# New_SERV_OPEN8_SOTB.net
KiCad netlist of a schematic drawn in EAGLE
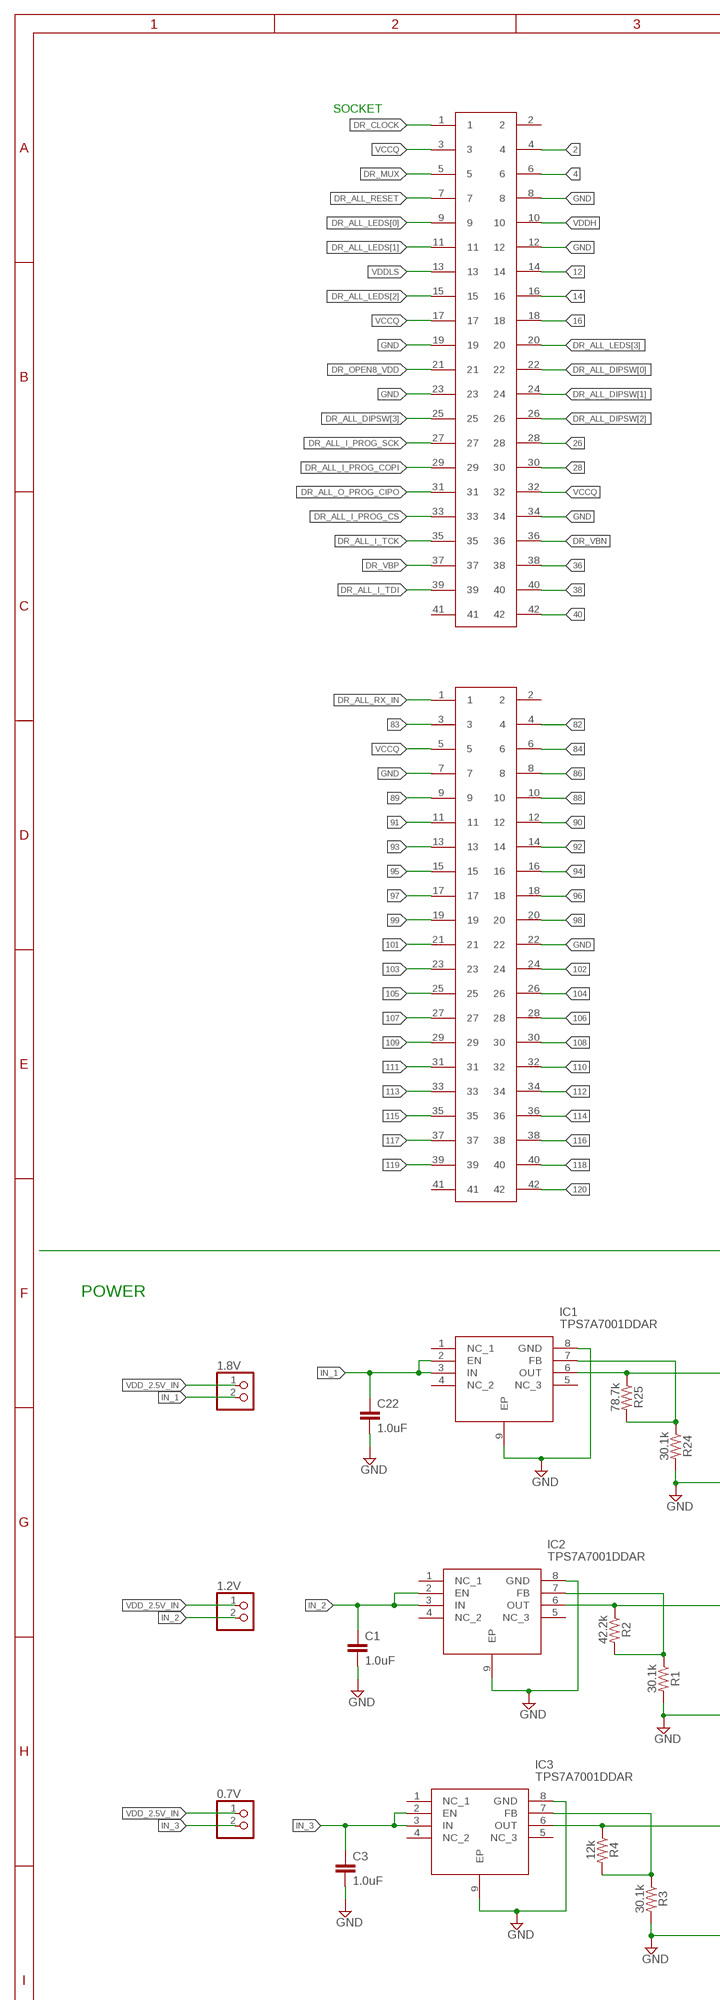
[diagram p0: schematic, sheet 1, part 1 of 2]
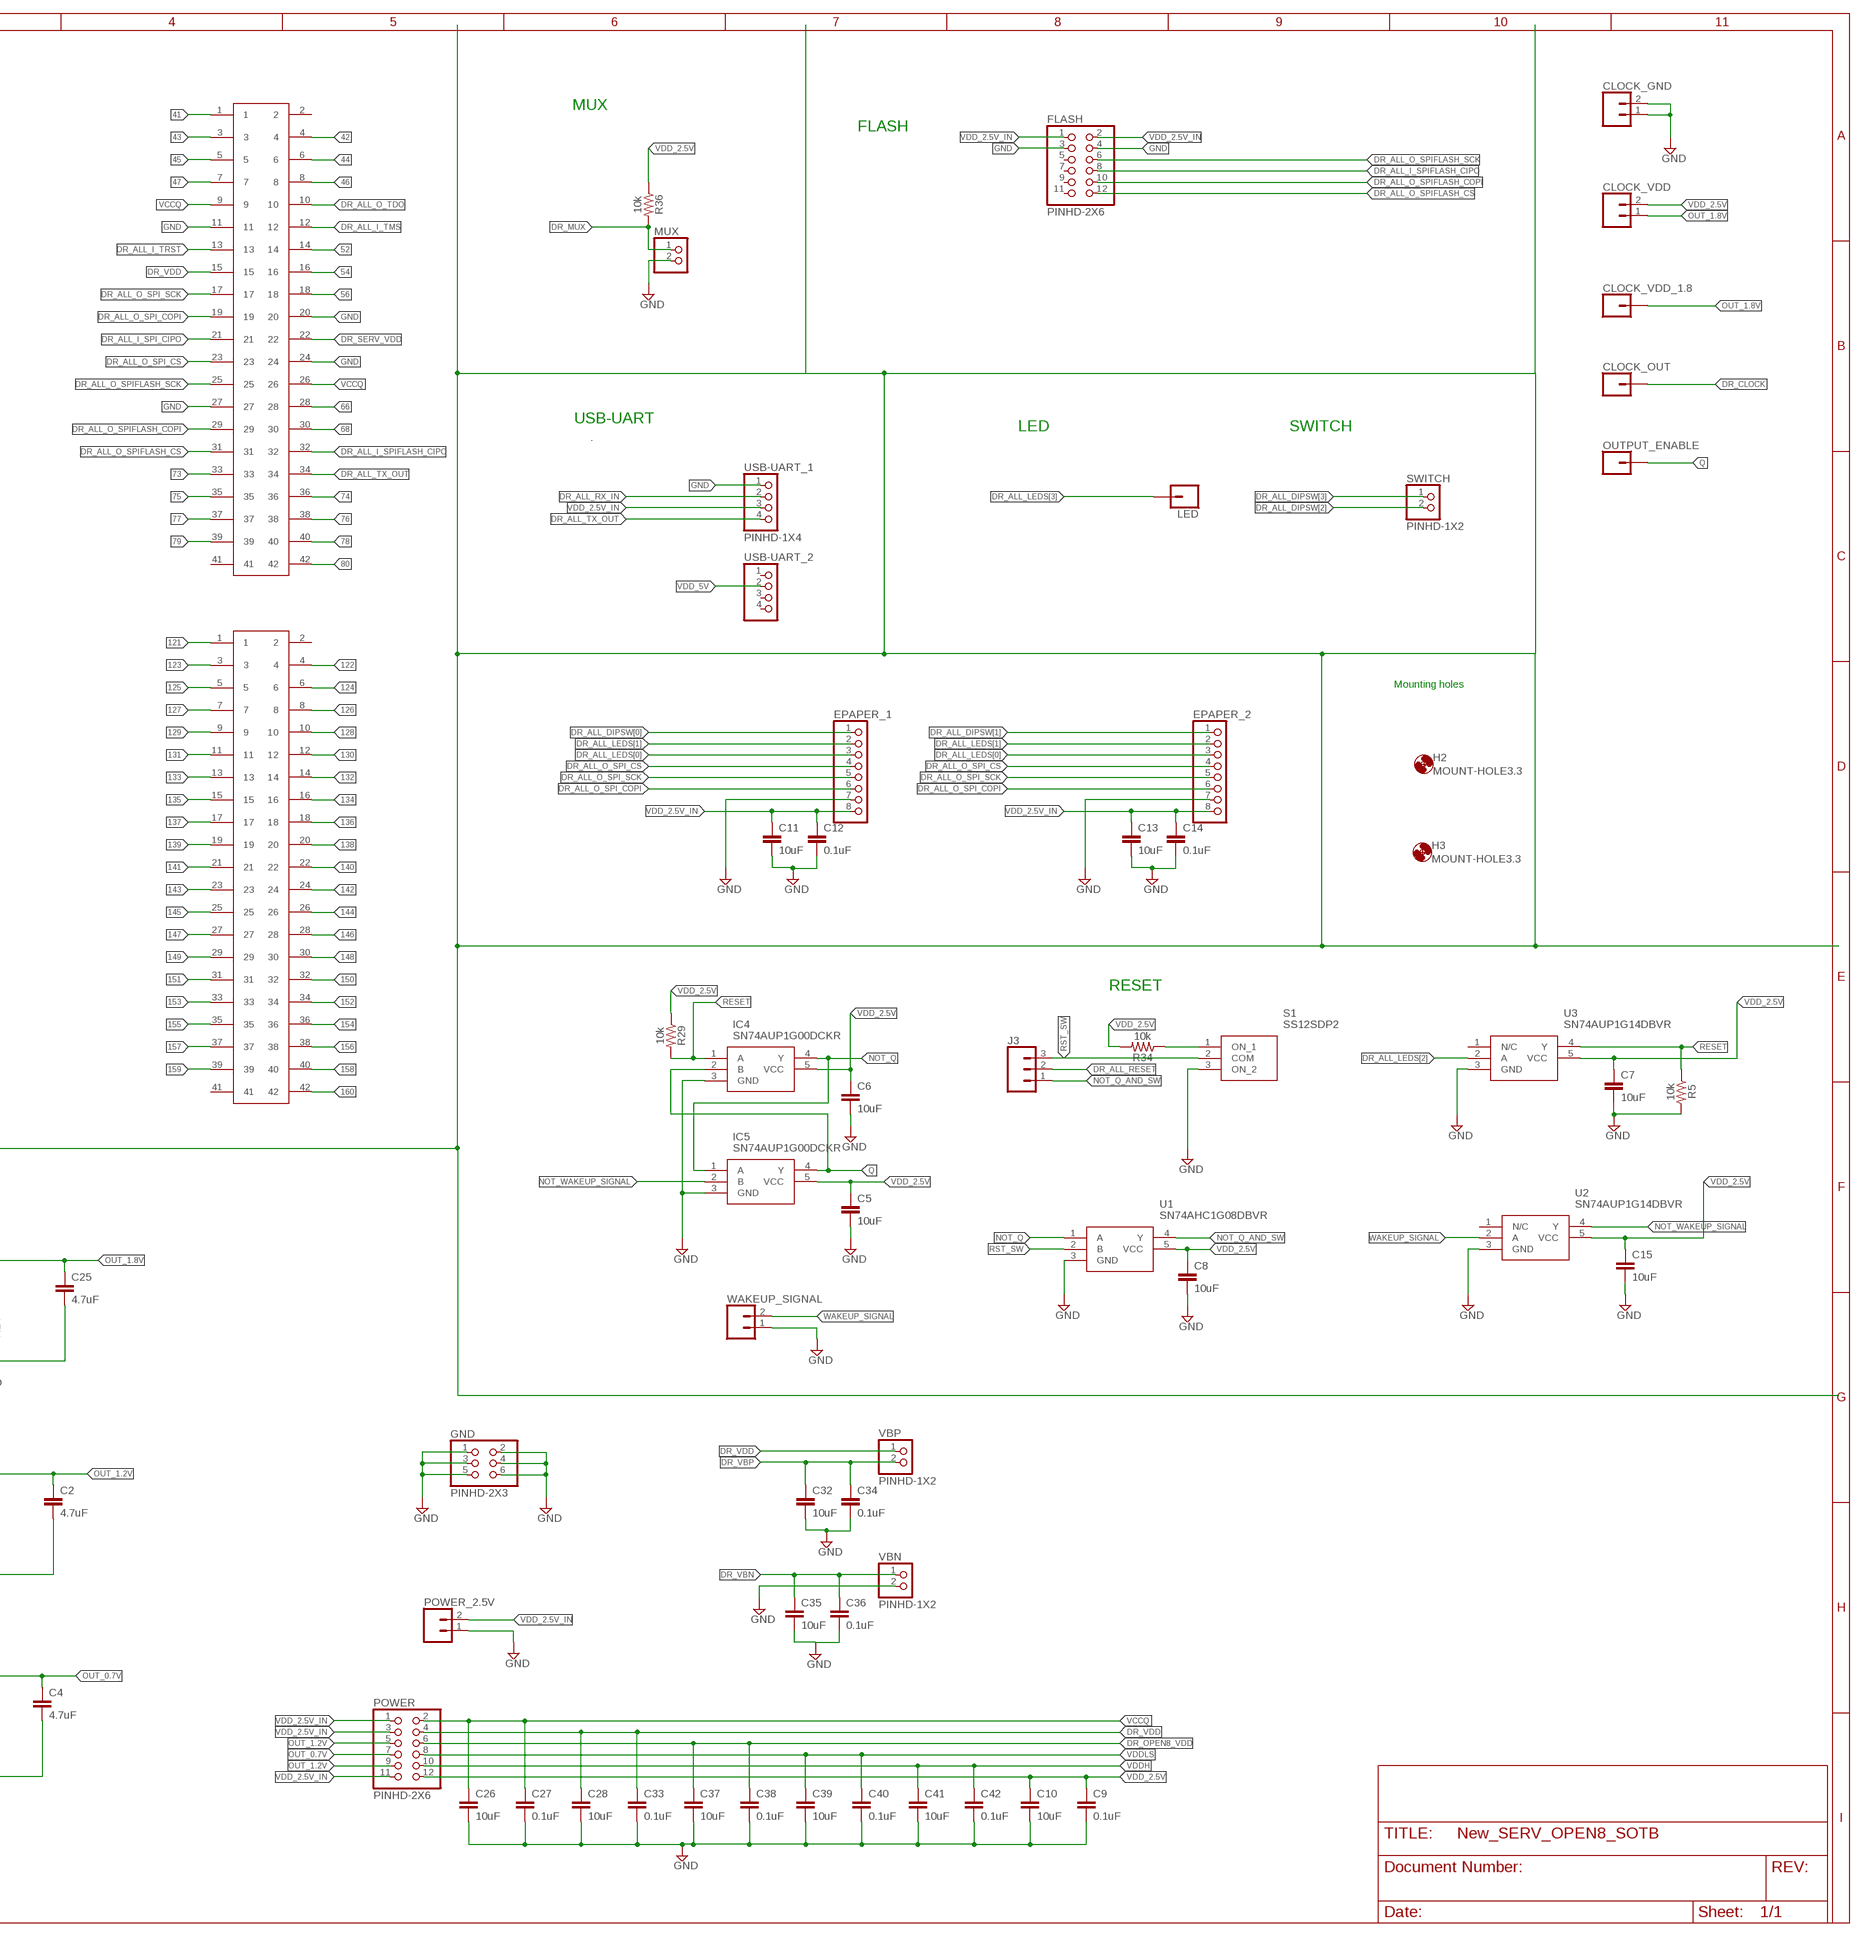
[diagram p1: schematic, sheet 1, part 2 of 2]

(export (version "E")
  (design (tool "Eeschema 10.0.6"))
  (components
    (comp (ref "0.7V")
      (value "PINHD-1X2")
      (footprint "eagle-import:1X02")
      (libsource (lib "eagle-import") (part "pinhead_325_PINHD-1X2"))
    )
    (comp (ref "1.2V")
      (value "PINHD-1X2")
      (footprint "eagle-import:1X02")
      (libsource (lib "eagle-import") (part "pinhead_325_PINHD-1X2"))
    )
    (comp (ref "1.8V")
      (value "PINHD-1X2")
      (footprint "eagle-import:1X02")
      (libsource (lib "eagle-import") (part "pinhead_325_PINHD-1X2"))
    )
    (comp (ref "C1")
      (value "1.0uF")
      (footprint "eagle-import:0805")
      (libsource (lib "eagle-import") (part "1.0UF-0805-25V-(+80/-20%)"))
    )
    (comp (ref "C2")
      (value "4.7uF")
      (footprint "eagle-import:0805")
      (libsource (lib "eagle-import") (part "1.0UF-0805-25V-(+80/-20%)"))
    )
    (comp (ref "C3")
      (value "1.0uF")
      (footprint "eagle-import:0805")
      (libsource (lib "eagle-import") (part "1.0UF-0805-25V-(+80/-20%)"))
    )
    (comp (ref "C4")
      (value "4.7uF")
      (footprint "eagle-import:0805")
      (libsource (lib "eagle-import") (part "1.0UF-0805-25V-(+80/-20%)"))
    )
    (comp (ref "C5")
      (value "10uF")
      (footprint "eagle-import:0805")
      (libsource (lib "eagle-import") (part "1.0UF-0805-25V-(+80/-20%)"))
    )
    (comp (ref "C6")
      (value "10uF")
      (footprint "eagle-import:0805")
      (libsource (lib "eagle-import") (part "1.0UF-0805-25V-(+80/-20%)"))
    )
    (comp (ref "C7")
      (value "10uF")
      (footprint "eagle-import:0805")
      (libsource (lib "eagle-import") (part "1.0UF-0805-25V-(+80/-20%)"))
    )
    (comp (ref "C8")
      (value "10uF")
      (footprint "eagle-import:0805")
      (libsource (lib "eagle-import") (part "1.0UF-0805-25V-(+80/-20%)"))
    )
    (comp (ref "C9")
      (value "0.1uF")
      (footprint "eagle-import:0805")
      (libsource (lib "eagle-import") (part "1.0UF-0805-25V-(+80/-20%)"))
    )
    (comp (ref "C10")
      (value "10uF")
      (footprint "eagle-import:0805")
      (libsource (lib "eagle-import") (part "1.0UF-0805-25V-(+80/-20%)"))
    )
    (comp (ref "C11")
      (value "10uF")
      (footprint "eagle-import:0805")
      (libsource (lib "eagle-import") (part "1.0UF-0805-25V-(+80/-20%)"))
    )
    (comp (ref "C12")
      (value "0.1uF")
      (footprint "eagle-import:0805")
      (libsource (lib "eagle-import") (part "1.0UF-0805-25V-(+80/-20%)"))
    )
    (comp (ref "C13")
      (value "10uF")
      (footprint "eagle-import:0805")
      (libsource (lib "eagle-import") (part "1.0UF-0805-25V-(+80/-20%)"))
    )
    (comp (ref "C14")
      (value "0.1uF")
      (footprint "eagle-import:0805")
      (libsource (lib "eagle-import") (part "1.0UF-0805-25V-(+80/-20%)"))
    )
    (comp (ref "C15")
      (value "10uF")
      (footprint "eagle-import:0805")
      (libsource (lib "eagle-import") (part "1.0UF-0805-25V-(+80/-20%)"))
    )
    (comp (ref "C22")
      (value "1.0uF")
      (footprint "eagle-import:0805")
      (libsource (lib "eagle-import") (part "1.0UF-0805-25V-(+80/-20%)"))
    )
    (comp (ref "C25")
      (value "4.7uF")
      (footprint "eagle-import:0805")
      (libsource (lib "eagle-import") (part "1.0UF-0805-25V-(+80/-20%)"))
    )
    (comp (ref "C26")
      (value "10uF")
      (footprint "eagle-import:0805")
      (libsource (lib "eagle-import") (part "1.0UF-0805-25V-(+80/-20%)"))
    )
    (comp (ref "C27")
      (value "0.1uF")
      (footprint "eagle-import:0805")
      (libsource (lib "eagle-import") (part "1.0UF-0805-25V-(+80/-20%)"))
    )
    (comp (ref "C28")
      (value "10uF")
      (footprint "eagle-import:0805")
      (libsource (lib "eagle-import") (part "1.0UF-0805-25V-(+80/-20%)"))
    )
    (comp (ref "C32")
      (value "10uF")
      (footprint "eagle-import:0805")
      (libsource (lib "eagle-import") (part "1.0UF-0805-25V-(+80/-20%)"))
    )
    (comp (ref "C33")
      (value "0.1uF")
      (footprint "eagle-import:0805")
      (libsource (lib "eagle-import") (part "1.0UF-0805-25V-(+80/-20%)"))
    )
    (comp (ref "C34")
      (value "0.1uF")
      (footprint "eagle-import:0805")
      (libsource (lib "eagle-import") (part "1.0UF-0805-25V-(+80/-20%)"))
    )
    (comp (ref "C35")
      (value "10uF")
      (footprint "eagle-import:0805")
      (libsource (lib "eagle-import") (part "1.0UF-0805-25V-(+80/-20%)"))
    )
    (comp (ref "C36")
      (value "0.1uF")
      (footprint "eagle-import:0805")
      (libsource (lib "eagle-import") (part "1.0UF-0805-25V-(+80/-20%)"))
    )
    (comp (ref "C37")
      (value "10uF")
      (footprint "eagle-import:0805")
      (libsource (lib "eagle-import") (part "1.0UF-0805-25V-(+80/-20%)"))
    )
    (comp (ref "C38")
      (value "0.1uF")
      (footprint "eagle-import:0805")
      (libsource (lib "eagle-import") (part "1.0UF-0805-25V-(+80/-20%)"))
    )
    (comp (ref "C39")
      (value "10uF")
      (footprint "eagle-import:0805")
      (libsource (lib "eagle-import") (part "1.0UF-0805-25V-(+80/-20%)"))
    )
    (comp (ref "C40")
      (value "0.1uF")
      (footprint "eagle-import:0805")
      (libsource (lib "eagle-import") (part "1.0UF-0805-25V-(+80/-20%)"))
    )
    (comp (ref "C41")
      (value "10uF")
      (footprint "eagle-import:0805")
      (libsource (lib "eagle-import") (part "1.0UF-0805-25V-(+80/-20%)"))
    )
    (comp (ref "C42")
      (value "0.1uF")
      (footprint "eagle-import:0805")
      (libsource (lib "eagle-import") (part "1.0UF-0805-25V-(+80/-20%)"))
    )
    (comp (ref "CLOCK_GND")
      (value "CONN_02")
      (footprint "eagle-import:1X02")
      (libsource (lib "eagle-import") (part "CONN_02"))
    )
    (comp (ref "CLOCK_OUT")
      (value "CONN_01")
      (footprint "eagle-import:1X01")
      (libsource (lib "eagle-import") (part "CONN_01"))
    )
    (comp (ref "CLOCK_VDD")
      (value "CONN_02")
      (footprint "eagle-import:1X02")
      (libsource (lib "eagle-import") (part "CONN_02"))
    )
    (comp (ref "CLOCK_VDD_1.8")
      (value "CONN_01")
      (footprint "eagle-import:1X01")
      (libsource (lib "eagle-import") (part "CONN_01"))
    )
    (comp (ref "EPAPER_1")
      (value "PINHD-1X8")
      (footprint "eagle-import:1X08")
      (libsource (lib "eagle-import") (part "PINHD-1X8"))
    )
    (comp (ref "EPAPER_2")
      (value "PINHD-1X8")
      (footprint "eagle-import:1X08")
      (libsource (lib "eagle-import") (part "PINHD-1X8"))
    )
    (comp (ref "FLASH")
      (value "PINHD-2X6")
      (footprint "eagle-import:2X06")
      (libsource (lib "eagle-import") (part "PINHD-2X6"))
    )
    (comp (ref "GND")
      (value "PINHD-2X3")
      (footprint "eagle-import:2X03")
      (libsource (lib "eagle-import") (part "PINHD-2X3"))
    )
    (comp (ref "H2")
      (value "MOUNT-HOLE3.3")
      (footprint "eagle-import:3,3")
      (libsource (lib "eagle-import") (part "MOUNT-HOLE3.3"))
    )
    (comp (ref "H3")
      (value "MOUNT-HOLE3.3")
      (footprint "eagle-import:3,3")
      (libsource (lib "eagle-import") (part "MOUNT-HOLE3.3"))
    )
    (comp (ref "IC1")
      (value "TPS7A7001DDAR")
      (footprint "eagle-import:SOIC127P600X170-9N")
      (fields (field (name "MOUSER_PART_NUMBER") "595-TPS7A7001DDAR"))
      (libsource (lib "eagle-import") (part "TPS7A7001DDAR"))
    )
    (comp (ref "IC2")
      (value "TPS7A7001DDAR")
      (footprint "eagle-import:SOIC127P600X170-9N")
      (fields (field (name "MOUSER_PART_NUMBER") "595-TPS7A7001DDAR"))
      (libsource (lib "eagle-import") (part "TPS7A7001DDAR"))
    )
    (comp (ref "IC3")
      (value "TPS7A7001DDAR")
      (footprint "eagle-import:SOIC127P600X170-9N")
      (fields (field (name "MOUSER_PART_NUMBER") "595-TPS7A7001DDAR"))
      (libsource (lib "eagle-import") (part "TPS7A7001DDAR"))
    )
    (comp (ref "IC4")
      (value "SN74AUP1G00DCKR")
      (footprint "eagle-import:SOT65P210X110-5N")
      (fields (field (name "MOUSER_PART_NUMBER") "595-SN74AUP1G00DCKR"))
      (libsource (lib "eagle-import") (part "SN74AUP1G00DCKR"))
    )
    (comp (ref "IC5")
      (value "SN74AUP1G00DCKR")
      (footprint "eagle-import:SOT65P210X110-5N")
      (fields (field (name "MOUSER_PART_NUMBER") "595-SN74AUP1G00DCKR"))
      (libsource (lib "eagle-import") (part "SN74AUP1G00DCKR"))
    )
    (comp (ref "J3")
      (value "CONN_03")
      (footprint "eagle-import:1X03")
      (libsource (lib "eagle-import") (part "CONN_03"))
    )
    (comp (ref "LED")
      (value "CONN_01")
      (footprint "eagle-import:1X01")
      (libsource (lib "eagle-import") (part "CONN_01"))
    )
    (comp (ref "MUX")
      (value "PINHD-1X2")
      (footprint "eagle-import:1X02")
      (libsource (lib "eagle-import") (part "pinhead_325_PINHD-1X2"))
    )
    (comp (ref "OUTPUT_ENABLE")
      (value "CONN_01")
      (footprint "eagle-import:1X01")
      (libsource (lib "eagle-import") (part "CONN_01"))
    )
    (comp (ref "POWER")
      (value "PINHD-2X6")
      (footprint "eagle-import:2X06")
      (libsource (lib "eagle-import") (part "PINHD-2X6"))
    )
    (comp (ref "POWER_2.5V")
      (value "CONN_02")
      (footprint "eagle-import:1X02")
      (libsource (lib "eagle-import") (part "CONN_02"))
    )
    (comp (ref "R1")
      (value "30.1k")
      (footprint "eagle-import:0805")
      (libsource (lib "eagle-import") (part "0.3OHM-0805-1/8W-1%"))
    )
    (comp (ref "R2")
      (value "42.2k")
      (footprint "eagle-import:0805")
      (libsource (lib "eagle-import") (part "0.3OHM-0805-1/8W-1%"))
    )
    (comp (ref "R3")
      (value "30.1k")
      (footprint "eagle-import:0805")
      (libsource (lib "eagle-import") (part "0.3OHM-0805-1/8W-1%"))
    )
    (comp (ref "R4")
      (value "12k")
      (footprint "eagle-import:0805")
      (libsource (lib "eagle-import") (part "0.3OHM-0805-1/8W-1%"))
    )
    (comp (ref "R5")
      (value "10k")
      (footprint "eagle-import:0805")
      (libsource (lib "eagle-import") (part "0.3OHM-0805-1/8W-1%"))
    )
    (comp (ref "R24")
      (value "30.1k")
      (footprint "eagle-import:0805")
      (libsource (lib "eagle-import") (part "0.3OHM-0805-1/8W-1%"))
    )
    (comp (ref "R25")
      (value "78.7k")
      (footprint "eagle-import:0805")
      (libsource (lib "eagle-import") (part "0.3OHM-0805-1/8W-1%"))
    )
    (comp (ref "R29")
      (value "10k")
      (footprint "eagle-import:0805")
      (libsource (lib "eagle-import") (part "0.3OHM-0805-1/8W-1%"))
    )
    (comp (ref "R34")
      (value "10k")
      (footprint "eagle-import:0805")
      (libsource (lib "eagle-import") (part "0.3OHM-0805-1/8W-1%"))
    )
    (comp (ref "R36")
      (value "10k")
      (footprint "eagle-import:0805")
      (libsource (lib "eagle-import") (part "0.3OHM-0805-1/8W-1%"))
    )
    (comp (ref "S1")
      (value "SS12SDP2")
      (footprint "eagle-import:SS12SDP2")
      (fields (field (name "MOUSER_PART_NUMBER") "633-SS12SDP2"))
      (libsource (lib "eagle-import") (part "SS12SDP2"))
    )
    (comp (ref "SWITCH")
      (value "PINHD-1X2")
      (footprint "eagle-import:1X02")
      (libsource (lib "eagle-import") (part "PINHD-1X2"))
    )
    (comp (ref "U$1")
      (value "2X41_HEADER")
      (footprint "eagle-import:2X41_HEADER")
      (libsource (lib "eagle-import") (part "2X41_HEADER"))
    )
    (comp (ref "U$2")
      (value "2X41_HEADER")
      (footprint "eagle-import:2X41_HEADER")
      (libsource (lib "eagle-import") (part "2X41_HEADER"))
    )
    (comp (ref "U$3")
      (value "2X41_HEADER")
      (footprint "eagle-import:2X41_HEADER")
      (libsource (lib "eagle-import") (part "2X41_HEADER"))
    )
    (comp (ref "U$4")
      (value "2X41_HEADER")
      (footprint "eagle-import:2X41_HEADER")
      (libsource (lib "eagle-import") (part "2X41_HEADER"))
    )
    (comp (ref "U1")
      (value "SN74AHC1G08DBVR")
      (footprint "eagle-import:SOT95P280X145-5N")
      (fields (field (name "MOUSER_PART_NUMBER") "595-SN74AHC1G08DBVR"))
      (libsource (lib "eagle-import") (part "SN74AHC1G08DBVR"))
    )
    (comp (ref "U2")
      (value "SN74AUP1G14DBVR")
      (footprint "eagle-import:SOT65P210X110-5N")
      (fields (field (name "MOUSER_PART_NUMBER") "595-SN74AUP1G14DBVR"))
      (libsource (lib "eagle-import") (part "SN74AUP1G14DBVR"))
    )
    (comp (ref "U3")
      (value "SN74AUP1G14DBVR")
      (footprint "eagle-import:SOT65P210X110-5N")
      (fields (field (name "MOUSER_PART_NUMBER") "595-SN74AUP1G14DBVR"))
      (libsource (lib "eagle-import") (part "SN74AUP1G14DBVR"))
    )
    (comp (ref "USB-UART_1")
      (value "PINHD-1X4")
      (footprint "eagle-import:1X04")
      (libsource (lib "eagle-import") (part "PINHD-1X4"))
    )
    (comp (ref "USB-UART_2")
      (value "PINHD-1X4")
      (footprint "eagle-import:1X04")
      (libsource (lib "eagle-import") (part "PINHD-1X4"))
    )
    (comp (ref "VBN")
      (value "PINHD-1X2")
      (footprint "eagle-import:1X02")
      (libsource (lib "eagle-import") (part "PINHD-1X2"))
    )
    (comp (ref "VBP")
      (value "PINHD-1X2")
      (footprint "eagle-import:1X02")
      (libsource (lib "eagle-import") (part "PINHD-1X2"))
    )
    (comp (ref "WAKEUP_SIGNAL")
      (value "CONN_02")
      (footprint "eagle-import:1X02")
      (libsource (lib "eagle-import") (part "CONN_02"))
    )
  )
  (nets
    (net (code "1") (name "2") (class "Default")
      (node (ref "U$1") (pin "4") (pinfunction "4_4") (pintype "bidirectional"))
    )
    (net (code "2") (name "4") (class "Default")
      (node (ref "U$1") (pin "6") (pinfunction "6_6") (pintype "bidirectional"))
    )
    (net (code "3") (name "12") (class "Default")
      (node (ref "U$1") (pin "14") (pinfunction "14_14") (pintype "bidirectional"))
    )
    (net (code "4") (name "14") (class "Default")
      (node (ref "U$1") (pin "16") (pinfunction "16_16") (pintype "bidirectional"))
    )
    (net (code "5") (name "16") (class "Default")
      (node (ref "U$1") (pin "18") (pinfunction "18_18") (pintype "bidirectional"))
    )
    (net (code "6") (name "26") (class "Default")
      (node (ref "U$1") (pin "28") (pinfunction "28_28") (pintype "bidirectional"))
    )
    (net (code "7") (name "28") (class "Default")
      (node (ref "U$1") (pin "30") (pinfunction "30_30") (pintype "bidirectional"))
    )
    (net (code "8") (name "36") (class "Default")
      (node (ref "U$1") (pin "38") (pinfunction "38_38") (pintype "bidirectional"))
    )
    (net (code "9") (name "38") (class "Default")
      (node (ref "U$1") (pin "40") (pinfunction "40_40") (pintype "bidirectional"))
    )
    (net (code "10") (name "40") (class "Default")
      (node (ref "U$1") (pin "42") (pinfunction "42_42") (pintype "bidirectional"))
    )
    (net (code "11") (name "41") (class "Default")
      (node (ref "U$2") (pin "1") (pinfunction "1_1") (pintype "bidirectional"))
    )
    (net (code "12") (name "42") (class "Default")
      (node (ref "U$2") (pin "4") (pinfunction "4_4") (pintype "bidirectional"))
    )
    (net (code "13") (name "43") (class "Default")
      (node (ref "U$2") (pin "3") (pinfunction "3_3") (pintype "bidirectional"))
    )
    (net (code "14") (name "44") (class "Default")
      (node (ref "U$2") (pin "6") (pinfunction "6_6") (pintype "bidirectional"))
    )
    (net (code "15") (name "45") (class "Default")
      (node (ref "U$2") (pin "5") (pinfunction "5_5") (pintype "bidirectional"))
    )
    (net (code "16") (name "46") (class "Default")
      (node (ref "U$2") (pin "8") (pinfunction "8_8") (pintype "bidirectional"))
    )
    (net (code "17") (name "47") (class "Default")
      (node (ref "U$2") (pin "7") (pinfunction "7_7") (pintype "bidirectional"))
    )
    (net (code "18") (name "52") (class "Default")
      (node (ref "U$2") (pin "14") (pinfunction "14_14") (pintype "bidirectional"))
    )
    (net (code "19") (name "54") (class "Default")
      (node (ref "U$2") (pin "16") (pinfunction "16_16") (pintype "bidirectional"))
    )
    (net (code "20") (name "56") (class "Default")
      (node (ref "U$2") (pin "18") (pinfunction "18_18") (pintype "bidirectional"))
    )
    (net (code "21") (name "66") (class "Default")
      (node (ref "U$2") (pin "28") (pinfunction "28_28") (pintype "bidirectional"))
    )
    (net (code "22") (name "68") (class "Default")
      (node (ref "U$2") (pin "30") (pinfunction "30_30") (pintype "bidirectional"))
    )
    (net (code "23") (name "73") (class "Default")
      (node (ref "U$2") (pin "33") (pinfunction "33_33") (pintype "bidirectional"))
    )
    (net (code "24") (name "74") (class "Default")
      (node (ref "U$2") (pin "36") (pinfunction "36_36") (pintype "bidirectional"))
    )
    (net (code "25") (name "75") (class "Default")
      (node (ref "U$2") (pin "35") (pinfunction "35_35") (pintype "bidirectional"))
    )
    (net (code "26") (name "76") (class "Default")
      (node (ref "U$2") (pin "38") (pinfunction "38_38") (pintype "bidirectional"))
    )
    (net (code "27") (name "77") (class "Default")
      (node (ref "U$2") (pin "37") (pinfunction "37_37") (pintype "bidirectional"))
    )
    (net (code "28") (name "78") (class "Default")
      (node (ref "U$2") (pin "40") (pinfunction "40_40") (pintype "bidirectional"))
    )
    (net (code "29") (name "79") (class "Default")
      (node (ref "U$2") (pin "39") (pinfunction "39_39") (pintype "bidirectional"))
    )
    (net (code "30") (name "80") (class "Default")
      (node (ref "U$2") (pin "42") (pinfunction "42_42") (pintype "bidirectional"))
    )
    (net (code "31") (name "82") (class "Default")
      (node (ref "U$3") (pin "4") (pinfunction "4_4") (pintype "bidirectional"))
    )
    (net (code "32") (name "83") (class "Default")
      (node (ref "U$3") (pin "3") (pinfunction "3_3") (pintype "bidirectional"))
    )
    (net (code "33") (name "84") (class "Default")
      (node (ref "U$3") (pin "6") (pinfunction "6_6") (pintype "bidirectional"))
    )
    (net (code "34") (name "86") (class "Default")
      (node (ref "U$3") (pin "8") (pinfunction "8_8") (pintype "bidirectional"))
    )
    (net (code "35") (name "88") (class "Default")
      (node (ref "U$3") (pin "10") (pinfunction "10_10") (pintype "bidirectional"))
    )
    (net (code "36") (name "89") (class "Default")
      (node (ref "U$3") (pin "9") (pinfunction "9_9") (pintype "bidirectional"))
    )
    (net (code "37") (name "90") (class "Default")
      (node (ref "U$3") (pin "12") (pinfunction "12_12") (pintype "bidirectional"))
    )
    (net (code "38") (name "91") (class "Default")
      (node (ref "U$3") (pin "11") (pinfunction "11_11") (pintype "bidirectional"))
    )
    (net (code "39") (name "92") (class "Default")
      (node (ref "U$3") (pin "14") (pinfunction "14_14") (pintype "bidirectional"))
    )
    (net (code "40") (name "93") (class "Default")
      (node (ref "U$3") (pin "13") (pinfunction "13_13") (pintype "bidirectional"))
    )
    (net (code "41") (name "94") (class "Default")
      (node (ref "U$3") (pin "16") (pinfunction "16_16") (pintype "bidirectional"))
    )
    (net (code "42") (name "95") (class "Default")
      (node (ref "U$3") (pin "15") (pinfunction "15_15") (pintype "bidirectional"))
    )
    (net (code "43") (name "96") (class "Default")
      (node (ref "U$3") (pin "18") (pinfunction "18_18") (pintype "bidirectional"))
    )
    (net (code "44") (name "97") (class "Default")
      (node (ref "U$3") (pin "17") (pinfunction "17_17") (pintype "bidirectional"))
    )
    (net (code "45") (name "98") (class "Default")
      (node (ref "U$3") (pin "20") (pinfunction "20_20") (pintype "bidirectional"))
    )
    (net (code "46") (name "99") (class "Default")
      (node (ref "U$3") (pin "19") (pinfunction "19_19") (pintype "bidirectional"))
    )
    (net (code "47") (name "101") (class "Default")
      (node (ref "U$3") (pin "21") (pinfunction "21_21") (pintype "bidirectional"))
    )
    (net (code "48") (name "102") (class "Default")
      (node (ref "U$3") (pin "24") (pinfunction "24_24") (pintype "bidirectional"))
    )
    (net (code "49") (name "103") (class "Default")
      (node (ref "U$3") (pin "23") (pinfunction "23_23") (pintype "bidirectional"))
    )
    (net (code "50") (name "104") (class "Default")
      (node (ref "U$3") (pin "26") (pinfunction "26_26") (pintype "bidirectional"))
    )
    (net (code "51") (name "105") (class "Default")
      (node (ref "U$3") (pin "25") (pinfunction "25_25") (pintype "bidirectional"))
    )
    (net (code "52") (name "106") (class "Default")
      (node (ref "U$3") (pin "28") (pinfunction "28_28") (pintype "bidirectional"))
    )
    (net (code "53") (name "107") (class "Default")
      (node (ref "U$3") (pin "27") (pinfunction "27_27") (pintype "bidirectional"))
    )
    (net (code "54") (name "108") (class "Default")
      (node (ref "U$3") (pin "30") (pinfunction "30_30") (pintype "bidirectional"))
    )
    (net (code "55") (name "109") (class "Default")
      (node (ref "U$3") (pin "29") (pinfunction "29_29") (pintype "bidirectional"))
    )
    (net (code "56") (name "110") (class "Default")
      (node (ref "U$3") (pin "32") (pinfunction "32_32") (pintype "bidirectional"))
    )
    (net (code "57") (name "111") (class "Default")
      (node (ref "U$3") (pin "31") (pinfunction "31_31") (pintype "bidirectional"))
    )
    (net (code "58") (name "112") (class "Default")
      (node (ref "U$3") (pin "34") (pinfunction "34_34") (pintype "bidirectional"))
    )
    (net (code "59") (name "113") (class "Default")
      (node (ref "U$3") (pin "33") (pinfunction "33_33") (pintype "bidirectional"))
    )
    (net (code "60") (name "114") (class "Default")
      (node (ref "U$3") (pin "36") (pinfunction "36_36") (pintype "bidirectional"))
    )
    (net (code "61") (name "115") (class "Default")
      (node (ref "U$3") (pin "35") (pinfunction "35_35") (pintype "bidirectional"))
    )
    (net (code "62") (name "116") (class "Default")
      (node (ref "U$3") (pin "38") (pinfunction "38_38") (pintype "bidirectional"))
    )
    (net (code "63") (name "117") (class "Default")
      (node (ref "U$3") (pin "37") (pinfunction "37_37") (pintype "bidirectional"))
    )
    (net (code "64") (name "118") (class "Default")
      (node (ref "U$3") (pin "40") (pinfunction "40_40") (pintype "bidirectional"))
    )
    (net (code "65") (name "119") (class "Default")
      (node (ref "U$3") (pin "39") (pinfunction "39_39") (pintype "bidirectional"))
    )
    (net (code "66") (name "120") (class "Default")
      (node (ref "U$3") (pin "42") (pinfunction "42_42") (pintype "bidirectional"))
    )
    (net (code "67") (name "121") (class "Default")
      (node (ref "U$4") (pin "1") (pinfunction "1_1") (pintype "bidirectional"))
    )
    (net (code "68") (name "122") (class "Default")
      (node (ref "U$4") (pin "4") (pinfunction "4_4") (pintype "bidirectional"))
    )
    (net (code "69") (name "123") (class "Default")
      (node (ref "U$4") (pin "3") (pinfunction "3_3") (pintype "bidirectional"))
    )
    (net (code "70") (name "124") (class "Default")
      (node (ref "U$4") (pin "6") (pinfunction "6_6") (pintype "bidirectional"))
    )
    (net (code "71") (name "125") (class "Default")
      (node (ref "U$4") (pin "5") (pinfunction "5_5") (pintype "bidirectional"))
    )
    (net (code "72") (name "126") (class "Default")
      (node (ref "U$4") (pin "8") (pinfunction "8_8") (pintype "bidirectional"))
    )
    (net (code "73") (name "127") (class "Default")
      (node (ref "U$4") (pin "7") (pinfunction "7_7") (pintype "bidirectional"))
    )
    (net (code "74") (name "128") (class "Default")
      (node (ref "U$4") (pin "10") (pinfunction "10_10") (pintype "bidirectional"))
    )
    (net (code "75") (name "129") (class "Default")
      (node (ref "U$4") (pin "9") (pinfunction "9_9") (pintype "bidirectional"))
    )
    (net (code "76") (name "130") (class "Default")
      (node (ref "U$4") (pin "12") (pinfunction "12_12") (pintype "bidirectional"))
    )
    (net (code "77") (name "131") (class "Default")
      (node (ref "U$4") (pin "11") (pinfunction "11_11") (pintype "bidirectional"))
    )
    (net (code "78") (name "132") (class "Default")
      (node (ref "U$4") (pin "14") (pinfunction "14_14") (pintype "bidirectional"))
    )
    (net (code "79") (name "133") (class "Default")
      (node (ref "U$4") (pin "13") (pinfunction "13_13") (pintype "bidirectional"))
    )
    (net (code "80") (name "134") (class "Default")
      (node (ref "U$4") (pin "16") (pinfunction "16_16") (pintype "bidirectional"))
    )
    (net (code "81") (name "135") (class "Default")
      (node (ref "U$4") (pin "15") (pinfunction "15_15") (pintype "bidirectional"))
    )
    (net (code "82") (name "136") (class "Default")
      (node (ref "U$4") (pin "18") (pinfunction "18_18") (pintype "bidirectional"))
    )
    (net (code "83") (name "137") (class "Default")
      (node (ref "U$4") (pin "17") (pinfunction "17_17") (pintype "bidirectional"))
    )
    (net (code "84") (name "138") (class "Default")
      (node (ref "U$4") (pin "20") (pinfunction "20_20") (pintype "bidirectional"))
    )
    (net (code "85") (name "139") (class "Default")
      (node (ref "U$4") (pin "19") (pinfunction "19_19") (pintype "bidirectional"))
    )
    (net (code "86") (name "140") (class "Default")
      (node (ref "U$4") (pin "22") (pinfunction "22_22") (pintype "bidirectional"))
    )
    (net (code "87") (name "141") (class "Default")
      (node (ref "U$4") (pin "21") (pinfunction "21_21") (pintype "bidirectional"))
    )
    (net (code "88") (name "142") (class "Default")
      (node (ref "U$4") (pin "24") (pinfunction "24_24") (pintype "bidirectional"))
    )
    (net (code "89") (name "143") (class "Default")
      (node (ref "U$4") (pin "23") (pinfunction "23_23") (pintype "bidirectional"))
    )
    (net (code "90") (name "144") (class "Default")
      (node (ref "U$4") (pin "26") (pinfunction "26_26") (pintype "bidirectional"))
    )
    (net (code "91") (name "145") (class "Default")
      (node (ref "U$4") (pin "25") (pinfunction "25_25") (pintype "bidirectional"))
    )
    (net (code "92") (name "146") (class "Default")
      (node (ref "U$4") (pin "28") (pinfunction "28_28") (pintype "bidirectional"))
    )
    (net (code "93") (name "147") (class "Default")
      (node (ref "U$4") (pin "27") (pinfunction "27_27") (pintype "bidirectional"))
    )
    (net (code "94") (name "148") (class "Default")
      (node (ref "U$4") (pin "30") (pinfunction "30_30") (pintype "bidirectional"))
    )
    (net (code "95") (name "149") (class "Default")
      (node (ref "U$4") (pin "29") (pinfunction "29_29") (pintype "bidirectional"))
    )
    (net (code "96") (name "150") (class "Default")
      (node (ref "U$4") (pin "32") (pinfunction "32_32") (pintype "bidirectional"))
    )
    (net (code "97") (name "151") (class "Default")
      (node (ref "U$4") (pin "31") (pinfunction "31_31") (pintype "bidirectional"))
    )
    (net (code "98") (name "152") (class "Default")
      (node (ref "U$4") (pin "34") (pinfunction "34_34") (pintype "bidirectional"))
    )
    (net (code "99") (name "153") (class "Default")
      (node (ref "U$4") (pin "33") (pinfunction "33_33") (pintype "bidirectional"))
    )
    (net (code "100") (name "154") (class "Default")
      (node (ref "U$4") (pin "36") (pinfunction "36_36") (pintype "bidirectional"))
    )
    (net (code "101") (name "155") (class "Default")
      (node (ref "U$4") (pin "35") (pinfunction "35_35") (pintype "bidirectional"))
    )
    (net (code "102") (name "156") (class "Default")
      (node (ref "U$4") (pin "38") (pinfunction "38_38") (pintype "bidirectional"))
    )
    (net (code "103") (name "157") (class "Default")
      (node (ref "U$4") (pin "37") (pinfunction "37_37") (pintype "bidirectional"))
    )
    (net (code "104") (name "158") (class "Default")
      (node (ref "U$4") (pin "40") (pinfunction "40_40") (pintype "bidirectional"))
    )
    (net (code "105") (name "159") (class "Default")
      (node (ref "U$4") (pin "39") (pinfunction "39_39") (pintype "bidirectional"))
    )
    (net (code "106") (name "160") (class "Default")
      (node (ref "U$4") (pin "42") (pinfunction "42_42") (pintype "bidirectional"))
    )
    (net (code "107") (name "DR_ALL_DIPSW[0]") (class "Default")
      (node (ref "EPAPER_1") (pin "1") (pinfunction "1_1") (pintype "passive"))
      (node (ref "U$1") (pin "22") (pinfunction "22_22") (pintype "bidirectional"))
    )
    (net (code "108") (name "DR_ALL_DIPSW[1]") (class "Default")
      (node (ref "EPAPER_2") (pin "1") (pinfunction "1_1") (pintype "passive"))
      (node (ref "U$1") (pin "24") (pinfunction "24_24") (pintype "bidirectional"))
    )
    (net (code "109") (name "DR_ALL_DIPSW[2]") (class "Default")
      (node (ref "SWITCH") (pin "2") (pinfunction "2_2") (pintype "passive"))
      (node (ref "U$1") (pin "26") (pinfunction "26_26") (pintype "bidirectional"))
    )
    (net (code "110") (name "DR_ALL_DIPSW[3]") (class "Default")
      (node (ref "SWITCH") (pin "1") (pinfunction "1_1") (pintype "passive"))
      (node (ref "U$1") (pin "25") (pinfunction "25_25") (pintype "bidirectional"))
    )
    (net (code "111") (name "DR_ALL_I_PROG_COPI") (class "Default")
      (node (ref "U$1") (pin "29") (pinfunction "29_29") (pintype "bidirectional"))
    )
    (net (code "112") (name "DR_ALL_I_PROG_CS") (class "Default")
      (node (ref "U$1") (pin "33") (pinfunction "33_33") (pintype "bidirectional"))
    )
    (net (code "113") (name "DR_ALL_I_PROG_SCK") (class "Default")
      (node (ref "U$1") (pin "27") (pinfunction "27_27") (pintype "bidirectional"))
    )
    (net (code "114") (name "DR_ALL_I_SPIFLASH_CIPO") (class "Default")
      (node (ref "FLASH") (pin "8") (pinfunction "8_8") (pintype "passive"))
      (node (ref "U$2") (pin "32") (pinfunction "32_32") (pintype "bidirectional"))
    )
    (net (code "115") (name "DR_ALL_I_SPI_CIPO") (class "Default")
      (node (ref "U$2") (pin "21") (pinfunction "21_21") (pintype "bidirectional"))
    )
    (net (code "116") (name "DR_ALL_I_TCK") (class "Default")
      (node (ref "U$1") (pin "35") (pinfunction "35_35") (pintype "bidirectional"))
    )
    (net (code "117") (name "DR_ALL_I_TDI") (class "Default")
      (node (ref "U$1") (pin "39") (pinfunction "39_39") (pintype "bidirectional"))
    )
    (net (code "118") (name "DR_ALL_I_TMS") (class "Default")
      (node (ref "U$2") (pin "12") (pinfunction "12_12") (pintype "bidirectional"))
    )
    (net (code "119") (name "DR_ALL_I_TRST") (class "Default")
      (node (ref "U$2") (pin "13") (pinfunction "13_13") (pintype "bidirectional"))
    )
    (net (code "120") (name "DR_ALL_LEDS[0]") (class "Default")
      (node (ref "EPAPER_1") (pin "3") (pinfunction "3_3") (pintype "passive"))
      (node (ref "EPAPER_2") (pin "3") (pinfunction "3_3") (pintype "passive"))
      (node (ref "U$1") (pin "9") (pinfunction "9_9") (pintype "bidirectional"))
    )
    (net (code "121") (name "DR_ALL_LEDS[1]") (class "Default")
      (node (ref "EPAPER_1") (pin "2") (pinfunction "2_2") (pintype "passive"))
      (node (ref "EPAPER_2") (pin "2") (pinfunction "2_2") (pintype "passive"))
      (node (ref "U$1") (pin "11") (pinfunction "11_11") (pintype "bidirectional"))
    )
    (net (code "122") (name "DR_ALL_LEDS[2]") (class "Default")
      (node (ref "U$1") (pin "15") (pinfunction "15_15") (pintype "bidirectional"))
      (node (ref "U3") (pin "2") (pinfunction "A_2") (pintype "input"))
    )
    (net (code "123") (name "DR_ALL_LEDS[3]") (class "Default")
      (node (ref "LED") (pin "1") (pinfunction "1_1") (pintype "passive"))
      (node (ref "U$1") (pin "20") (pinfunction "20_20") (pintype "bidirectional"))
    )
    (net (code "124") (name "DR_ALL_O_PROG_CIPO") (class "Default")
      (node (ref "U$1") (pin "31") (pinfunction "31_31") (pintype "bidirectional"))
    )
    (net (code "125") (name "DR_ALL_O_SPIFLASH_COPI") (class "Default")
      (node (ref "FLASH") (pin "10") (pinfunction "10_10") (pintype "passive"))
      (node (ref "U$2") (pin "29") (pinfunction "29_29") (pintype "bidirectional"))
    )
    (net (code "126") (name "DR_ALL_O_SPIFLASH_CS") (class "Default")
      (node (ref "FLASH") (pin "12") (pinfunction "12_12") (pintype "passive"))
      (node (ref "U$2") (pin "31") (pinfunction "31_31") (pintype "bidirectional"))
    )
    (net (code "127") (name "DR_ALL_O_SPIFLASH_SCK") (class "Default")
      (node (ref "FLASH") (pin "6") (pinfunction "6_6") (pintype "passive"))
      (node (ref "U$2") (pin "25") (pinfunction "25_25") (pintype "bidirectional"))
    )
    (net (code "128") (name "DR_ALL_O_SPI_COPI") (class "Default")
      (node (ref "EPAPER_1") (pin "6") (pinfunction "6_6") (pintype "passive"))
      (node (ref "EPAPER_2") (pin "6") (pinfunction "6_6") (pintype "passive"))
      (node (ref "U$2") (pin "19") (pinfunction "19_19") (pintype "bidirectional"))
    )
    (net (code "129") (name "DR_ALL_O_SPI_CS") (class "Default")
      (node (ref "EPAPER_1") (pin "4") (pinfunction "4_4") (pintype "passive"))
      (node (ref "EPAPER_2") (pin "4") (pinfunction "4_4") (pintype "passive"))
      (node (ref "U$2") (pin "23") (pinfunction "23_23") (pintype "bidirectional"))
    )
    (net (code "130") (name "DR_ALL_O_SPI_SCK") (class "Default")
      (node (ref "EPAPER_1") (pin "5") (pinfunction "5_5") (pintype "passive"))
      (node (ref "EPAPER_2") (pin "5") (pinfunction "5_5") (pintype "passive"))
      (node (ref "U$2") (pin "17") (pinfunction "17_17") (pintype "bidirectional"))
    )
    (net (code "131") (name "DR_ALL_O_TDO") (class "Default")
      (node (ref "U$2") (pin "10") (pinfunction "10_10") (pintype "bidirectional"))
    )
    (net (code "132") (name "DR_ALL_RESET") (class "Default")
      (node (ref "J3") (pin "2") (pinfunction "2_2") (pintype "passive"))
      (node (ref "U$1") (pin "7") (pinfunction "7_7") (pintype "bidirectional"))
    )
    (net (code "133") (name "DR_ALL_RX_IN") (class "Default")
      (node (ref "U$3") (pin "1") (pinfunction "1_1") (pintype "bidirectional"))
      (node (ref "USB-UART_1") (pin "2") (pinfunction "2_2") (pintype "passive"))
    )
    (net (code "134") (name "DR_ALL_TX_OUT") (class "Default")
      (node (ref "U$2") (pin "34") (pinfunction "34_34") (pintype "bidirectional"))
      (node (ref "USB-UART_1") (pin "4") (pinfunction "4_4") (pintype "passive"))
    )
    (net (code "135") (name "DR_CLOCK") (class "Default")
      (node (ref "CLOCK_OUT") (pin "1") (pinfunction "1_1") (pintype "passive"))
      (node (ref "U$1") (pin "1") (pinfunction "1_1") (pintype "bidirectional"))
    )
    (net (code "136") (name "DR_MUX") (class "Default")
      (node (ref "MUX") (pin "1") (pinfunction "1_1") (pintype "passive"))
      (node (ref "R36") (pin "2") (pinfunction "2_2") (pintype "passive"))
      (node (ref "U$1") (pin "5") (pinfunction "5_5") (pintype "bidirectional"))
    )
    (net (code "137") (name "DR_OPEN8_VDD") (class "Default")
      (node (ref "C37") (pin "1") (pinfunction "1_1") (pintype "passive"))
      (node (ref "C38") (pin "1") (pinfunction "1_1") (pintype "passive"))
      (node (ref "POWER") (pin "6") (pinfunction "6_6") (pintype "passive"))
      (node (ref "U$1") (pin "21") (pinfunction "21_21") (pintype "bidirectional"))
    )
    (net (code "138") (name "DR_SERV_VDD") (class "Default")
      (node (ref "U$2") (pin "22") (pinfunction "22_22") (pintype "bidirectional"))
    )
    (net (code "139") (name "DR_VBN") (class "Default")
      (node (ref "C35") (pin "1") (pinfunction "1_1") (pintype "passive"))
      (node (ref "C36") (pin "1") (pinfunction "1_1") (pintype "passive"))
      (node (ref "U$1") (pin "36") (pinfunction "36_36") (pintype "bidirectional"))
      (node (ref "VBN") (pin "1") (pinfunction "1_1") (pintype "passive"))
    )
    (net (code "140") (name "DR_VBP") (class "Default")
      (node (ref "C32") (pin "1") (pinfunction "1_1") (pintype "passive"))
      (node (ref "C34") (pin "1") (pinfunction "1_1") (pintype "passive"))
      (node (ref "U$1") (pin "37") (pinfunction "37_37") (pintype "bidirectional"))
      (node (ref "VBP") (pin "2") (pinfunction "2_2") (pintype "passive"))
    )
    (net (code "141") (name "DR_VDD") (class "Default")
      (node (ref "C28") (pin "1") (pinfunction "1_1") (pintype "passive"))
      (node (ref "C33") (pin "1") (pinfunction "1_1") (pintype "passive"))
      (node (ref "POWER") (pin "4") (pinfunction "4_4") (pintype "passive"))
      (node (ref "U$2") (pin "15") (pinfunction "15_15") (pintype "bidirectional"))
      (node (ref "VBP") (pin "1") (pinfunction "1_1") (pintype "passive"))
    )
    (net (code "142") (name "GND") (class "Default")
      (node (ref "C1") (pin "2") (pinfunction "2_2") (pintype "passive"))
      (node (ref "C10") (pin "2") (pinfunction "2_2") (pintype "passive"))
      (node (ref "C11") (pin "2") (pinfunction "2_2") (pintype "passive"))
      (node (ref "C12") (pin "2") (pinfunction "2_2") (pintype "passive"))
      (node (ref "C13") (pin "2") (pinfunction "2_2") (pintype "passive"))
      (node (ref "C14") (pin "2") (pinfunction "2_2") (pintype "passive"))
      (node (ref "C15") (pin "2") (pinfunction "2_2") (pintype "passive"))
      (node (ref "C2") (pin "2") (pinfunction "2_2") (pintype "passive"))
      (node (ref "C22") (pin "2") (pinfunction "2_2") (pintype "passive"))
      (node (ref "C25") (pin "2") (pinfunction "2_2") (pintype "passive"))
      (node (ref "C26") (pin "2") (pinfunction "2_2") (pintype "passive"))
      (node (ref "C27") (pin "2") (pinfunction "2_2") (pintype "passive"))
      (node (ref "C28") (pin "2") (pinfunction "2_2") (pintype "passive"))
      (node (ref "C3") (pin "2") (pinfunction "2_2") (pintype "passive"))
      (node (ref "C32") (pin "2") (pinfunction "2_2") (pintype "passive"))
      (node (ref "C33") (pin "2") (pinfunction "2_2") (pintype "passive"))
      (node (ref "C34") (pin "2") (pinfunction "2_2") (pintype "passive"))
      (node (ref "C35") (pin "2") (pinfunction "2_2") (pintype "passive"))
      (node (ref "C36") (pin "2") (pinfunction "2_2") (pintype "passive"))
      (node (ref "C37") (pin "2") (pinfunction "2_2") (pintype "passive"))
      (node (ref "C38") (pin "2") (pinfunction "2_2") (pintype "passive"))
      (node (ref "C39") (pin "2") (pinfunction "2_2") (pintype "passive"))
      (node (ref "C4") (pin "2") (pinfunction "2_2") (pintype "passive"))
      (node (ref "C40") (pin "2") (pinfunction "2_2") (pintype "passive"))
      (node (ref "C41") (pin "2") (pinfunction "2_2") (pintype "passive"))
      (node (ref "C42") (pin "2") (pinfunction "2_2") (pintype "passive"))
      (node (ref "C5") (pin "2") (pinfunction "2_2") (pintype "passive"))
      (node (ref "C6") (pin "2") (pinfunction "2_2") (pintype "passive"))
      (node (ref "C7") (pin "2") (pinfunction "2_2") (pintype "passive"))
      (node (ref "C8") (pin "2") (pinfunction "2_2") (pintype "passive"))
      (node (ref "C9") (pin "2") (pinfunction "2_2") (pintype "passive"))
      (node (ref "CLOCK_GND") (pin "1") (pinfunction "1_1") (pintype "passive"))
      (node (ref "CLOCK_GND") (pin "2") (pinfunction "2_2") (pintype "passive"))
      (node (ref "EPAPER_1") (pin "7") (pinfunction "7_7") (pintype "passive"))
      (node (ref "EPAPER_2") (pin "7") (pinfunction "7_7") (pintype "passive"))
      (node (ref "FLASH") (pin "3") (pinfunction "3_3") (pintype "passive"))
      (node (ref "FLASH") (pin "4") (pinfunction "4_4") (pintype "passive"))
      (node (ref "GND") (pin "1") (pinfunction "1_1") (pintype "passive"))
      (node (ref "GND") (pin "2") (pinfunction "2_2") (pintype "passive"))
      (node (ref "GND") (pin "3") (pinfunction "3_3") (pintype "passive"))
      (node (ref "GND") (pin "4") (pinfunction "4_4") (pintype "passive"))
      (node (ref "GND") (pin "5") (pinfunction "5_5") (pintype "passive"))
      (node (ref "GND") (pin "6") (pinfunction "6_6") (pintype "passive"))
      (node (ref "IC1") (pin "8") (pinfunction "GND_8") (pintype "bidirectional"))
      (node (ref "IC1") (pin "9") (pinfunction "EP_9") (pintype "bidirectional"))
      (node (ref "IC2") (pin "8") (pinfunction "GND_8") (pintype "bidirectional"))
      (node (ref "IC2") (pin "9") (pinfunction "EP_9") (pintype "bidirectional"))
      (node (ref "IC3") (pin "8") (pinfunction "GND_8") (pintype "bidirectional"))
      (node (ref "IC3") (pin "9") (pinfunction "EP_9") (pintype "bidirectional"))
      (node (ref "IC4") (pin "3") (pinfunction "GND_3") (pintype "bidirectional"))
      (node (ref "IC5") (pin "3") (pinfunction "GND_3") (pintype "bidirectional"))
      (node (ref "MUX") (pin "2") (pinfunction "2_2") (pintype "passive"))
      (node (ref "POWER_2.5V") (pin "1") (pinfunction "1_1") (pintype "passive"))
      (node (ref "R1") (pin "2") (pinfunction "2_2") (pintype "passive"))
      (node (ref "R24") (pin "2") (pinfunction "2_2") (pintype "passive"))
      (node (ref "R3") (pin "2") (pinfunction "2_2") (pintype "passive"))
      (node (ref "R5") (pin "2") (pinfunction "2_2") (pintype "passive"))
      (node (ref "S1") (pin "3") (pinfunction "ON_2_3") (pintype "bidirectional"))
      (node (ref "U$1") (pin "12") (pinfunction "12_12") (pintype "bidirectional"))
      (node (ref "U$1") (pin "19") (pinfunction "19_19") (pintype "bidirectional"))
      (node (ref "U$1") (pin "23") (pinfunction "23_23") (pintype "bidirectional"))
      (node (ref "U$1") (pin "34") (pinfunction "34_34") (pintype "bidirectional"))
      (node (ref "U$1") (pin "8") (pinfunction "8_8") (pintype "bidirectional"))
      (node (ref "U$2") (pin "11") (pinfunction "11_11") (pintype "bidirectional"))
      (node (ref "U$2") (pin "20") (pinfunction "20_20") (pintype "bidirectional"))
      (node (ref "U$2") (pin "24") (pinfunction "24_24") (pintype "bidirectional"))
      (node (ref "U$2") (pin "27") (pinfunction "27_27") (pintype "bidirectional"))
      (node (ref "U$3") (pin "22") (pinfunction "22_22") (pintype "bidirectional"))
      (node (ref "U$3") (pin "7") (pinfunction "7_7") (pintype "bidirectional"))
      (node (ref "U1") (pin "3") (pinfunction "GND_3") (pintype "bidirectional"))
      (node (ref "U2") (pin "3") (pinfunction "GND_3") (pintype "power_in"))
      (node (ref "U3") (pin "3") (pinfunction "GND_3") (pintype "power_in"))
      (node (ref "USB-UART_1") (pin "1") (pinfunction "1_1") (pintype "passive"))
      (node (ref "VBN") (pin "2") (pinfunction "2_2") (pintype "passive"))
      (node (ref "WAKEUP_SIGNAL") (pin "1") (pinfunction "1_1") (pintype "passive"))
    )
    (net (code "143") (name "IN_1") (class "Default")
      (node (ref "1.8V") (pin "2") (pinfunction "2_2") (pintype "passive"))
      (node (ref "C22") (pin "1") (pinfunction "1_1") (pintype "passive"))
      (node (ref "IC1") (pin "2") (pinfunction "EN_2") (pintype "bidirectional"))
      (node (ref "IC1") (pin "3") (pinfunction "IN_3") (pintype "bidirectional"))
    )
    (net (code "144") (name "IN_2") (class "Default")
      (node (ref "1.2V") (pin "2") (pinfunction "2_2") (pintype "passive"))
      (node (ref "C1") (pin "1") (pinfunction "1_1") (pintype "passive"))
      (node (ref "IC2") (pin "2") (pinfunction "EN_2") (pintype "bidirectional"))
      (node (ref "IC2") (pin "3") (pinfunction "IN_3") (pintype "bidirectional"))
    )
    (net (code "145") (name "IN_3") (class "Default")
      (node (ref "0.7V") (pin "2") (pinfunction "2_2") (pintype "passive"))
      (node (ref "C3") (pin "1") (pinfunction "1_1") (pintype "passive"))
      (node (ref "IC3") (pin "2") (pinfunction "EN_2") (pintype "bidirectional"))
      (node (ref "IC3") (pin "3") (pinfunction "IN_3") (pintype "bidirectional"))
    )
    (net (code "146") (name "NOT_Q") (class "Default")
      (node (ref "IC4") (pin "4") (pinfunction "Y_4") (pintype "bidirectional"))
      (node (ref "IC5") (pin "1") (pinfunction "A_1") (pintype "bidirectional"))
      (node (ref "U1") (pin "1") (pinfunction "A_1") (pintype "bidirectional"))
    )
    (net (code "147") (name "NOT_Q_AND_SW") (class "Default")
      (node (ref "J3") (pin "1") (pinfunction "1_1") (pintype "passive"))
      (node (ref "U1") (pin "4") (pinfunction "Y_4") (pintype "bidirectional"))
    )
    (net (code "148") (name "NOT_WAKEUP_SIGNAL") (class "Default")
      (node (ref "IC5") (pin "2") (pinfunction "B_2") (pintype "bidirectional"))
      (node (ref "U2") (pin "4") (pinfunction "Y_4") (pintype "output"))
    )
    (net (code "149") (name "Net-(IC1-FB)") (class "Default")
      (node (ref "IC1") (pin "7") (pinfunction "FB_7") (pintype "bidirectional"))
      (node (ref "R24") (pin "1") (pinfunction "1_1") (pintype "passive"))
      (node (ref "R25") (pin "2") (pinfunction "2_2") (pintype "passive"))
    )
    (net (code "150") (name "Net-(IC2-FB)") (class "Default")
      (node (ref "IC2") (pin "7") (pinfunction "FB_7") (pintype "bidirectional"))
      (node (ref "R1") (pin "1") (pinfunction "1_1") (pintype "passive"))
      (node (ref "R2") (pin "2") (pinfunction "2_2") (pintype "passive"))
    )
    (net (code "151") (name "Net-(IC3-FB)") (class "Default")
      (node (ref "IC3") (pin "7") (pinfunction "FB_7") (pintype "bidirectional"))
      (node (ref "R3") (pin "1") (pinfunction "1_1") (pintype "passive"))
      (node (ref "R4") (pin "2") (pinfunction "2_2") (pintype "passive"))
    )
    (net (code "152") (name "Net-(S1-ON_1)") (class "Default")
      (node (ref "R34") (pin "1") (pinfunction "1_1") (pintype "passive"))
      (node (ref "S1") (pin "1") (pinfunction "ON_1_1") (pintype "bidirectional"))
    )
    (net (code "153") (name "OUT_0.7V") (class "Default")
      (node (ref "C4") (pin "1") (pinfunction "1_1") (pintype "passive"))
      (node (ref "IC3") (pin "6") (pinfunction "OUT_6") (pintype "bidirectional"))
      (node (ref "POWER") (pin "7") (pinfunction "7_7") (pintype "passive"))
      (node (ref "R4") (pin "1") (pinfunction "1_1") (pintype "passive"))
    )
    (net (code "154") (name "OUT_1.2V") (class "Default")
      (node (ref "C2") (pin "1") (pinfunction "1_1") (pintype "passive"))
      (node (ref "IC2") (pin "6") (pinfunction "OUT_6") (pintype "bidirectional"))
      (node (ref "POWER") (pin "5") (pinfunction "5_5") (pintype "passive"))
      (node (ref "POWER") (pin "9") (pinfunction "9_9") (pintype "passive"))
      (node (ref "R2") (pin "1") (pinfunction "1_1") (pintype "passive"))
    )
    (net (code "155") (name "OUT_1.8V") (class "Default")
      (node (ref "C25") (pin "1") (pinfunction "1_1") (pintype "passive"))
      (node (ref "CLOCK_VDD") (pin "1") (pinfunction "1_1") (pintype "passive"))
      (node (ref "CLOCK_VDD_1.8") (pin "1") (pinfunction "1_1") (pintype "passive"))
      (node (ref "IC1") (pin "6") (pinfunction "OUT_6") (pintype "bidirectional"))
      (node (ref "R25") (pin "1") (pinfunction "1_1") (pintype "passive"))
    )
    (net (code "156") (name "Q") (class "Default")
      (node (ref "IC4") (pin "2") (pinfunction "B_2") (pintype "bidirectional"))
      (node (ref "IC5") (pin "4") (pinfunction "Y_4") (pintype "bidirectional"))
      (node (ref "OUTPUT_ENABLE") (pin "1") (pinfunction "1_1") (pintype "passive"))
    )
    (net (code "157") (name "RESET") (class "Default")
      (node (ref "IC4") (pin "1") (pinfunction "A_1") (pintype "bidirectional"))
      (node (ref "R29") (pin "2") (pinfunction "2_2") (pintype "passive"))
      (node (ref "R5") (pin "1") (pinfunction "1_1") (pintype "passive"))
      (node (ref "U3") (pin "4") (pinfunction "Y_4") (pintype "output"))
    )
    (net (code "158") (name "RST_SW") (class "Default")
      (node (ref "J3") (pin "3") (pinfunction "3_3") (pintype "passive"))
      (node (ref "S1") (pin "2") (pinfunction "COM_2") (pintype "bidirectional"))
      (node (ref "U1") (pin "2") (pinfunction "B_2") (pintype "bidirectional"))
    )
    (net (code "159") (name "VCCQ") (class "Default")
      (node (ref "C26") (pin "1") (pinfunction "1_1") (pintype "passive"))
      (node (ref "C27") (pin "1") (pinfunction "1_1") (pintype "passive"))
      (node (ref "POWER") (pin "2") (pinfunction "2_2") (pintype "passive"))
      (node (ref "U$1") (pin "17") (pinfunction "17_17") (pintype "bidirectional"))
      (node (ref "U$1") (pin "3") (pinfunction "3_3") (pintype "bidirectional"))
      (node (ref "U$1") (pin "32") (pinfunction "32_32") (pintype "bidirectional"))
      (node (ref "U$2") (pin "26") (pinfunction "26_26") (pintype "bidirectional"))
      (node (ref "U$2") (pin "9") (pinfunction "9_9") (pintype "bidirectional"))
      (node (ref "U$3") (pin "5") (pinfunction "5_5") (pintype "bidirectional"))
    )
    (net (code "160") (name "VDDH") (class "Default")
      (node (ref "C41") (pin "1") (pinfunction "1_1") (pintype "passive"))
      (node (ref "C42") (pin "1") (pinfunction "1_1") (pintype "passive"))
      (node (ref "POWER") (pin "10") (pinfunction "10_10") (pintype "passive"))
      (node (ref "U$1") (pin "10") (pinfunction "10_10") (pintype "bidirectional"))
    )
    (net (code "161") (name "VDDLS") (class "Default")
      (node (ref "C39") (pin "1") (pinfunction "1_1") (pintype "passive"))
      (node (ref "C40") (pin "1") (pinfunction "1_1") (pintype "passive"))
      (node (ref "POWER") (pin "8") (pinfunction "8_8") (pintype "passive"))
      (node (ref "U$1") (pin "13") (pinfunction "13_13") (pintype "bidirectional"))
    )
    (net (code "162") (name "VDD_2.5V") (class "Default")
      (node (ref "C10") (pin "1") (pinfunction "1_1") (pintype "passive"))
      (node (ref "C15") (pin "1") (pinfunction "1_1") (pintype "passive"))
      (node (ref "C5") (pin "1") (pinfunction "1_1") (pintype "passive"))
      (node (ref "C6") (pin "1") (pinfunction "1_1") (pintype "passive"))
      (node (ref "C7") (pin "1") (pinfunction "1_1") (pintype "passive"))
      (node (ref "C8") (pin "1") (pinfunction "1_1") (pintype "passive"))
      (node (ref "C9") (pin "1") (pinfunction "1_1") (pintype "passive"))
      (node (ref "CLOCK_VDD") (pin "2") (pinfunction "2_2") (pintype "passive"))
      (node (ref "IC4") (pin "5") (pinfunction "VCC_5") (pintype "bidirectional"))
      (node (ref "IC5") (pin "5") (pinfunction "VCC_5") (pintype "bidirectional"))
      (node (ref "POWER") (pin "12") (pinfunction "12_12") (pintype "passive"))
      (node (ref "R29") (pin "1") (pinfunction "1_1") (pintype "passive"))
      (node (ref "R34") (pin "2") (pinfunction "2_2") (pintype "passive"))
      (node (ref "R36") (pin "1") (pinfunction "1_1") (pintype "passive"))
      (node (ref "U1") (pin "5") (pinfunction "VCC_5") (pintype "bidirectional"))
      (node (ref "U2") (pin "5") (pinfunction "VCC_5") (pintype "power_in"))
      (node (ref "U3") (pin "5") (pinfunction "VCC_5") (pintype "power_in"))
    )
    (net (code "163") (name "VDD_2.5V_IN") (class "Default")
      (node (ref "0.7V") (pin "1") (pinfunction "1_1") (pintype "passive"))
      (node (ref "1.2V") (pin "1") (pinfunction "1_1") (pintype "passive"))
      (node (ref "1.8V") (pin "1") (pinfunction "1_1") (pintype "passive"))
      (node (ref "C11") (pin "1") (pinfunction "1_1") (pintype "passive"))
      (node (ref "C12") (pin "1") (pinfunction "1_1") (pintype "passive"))
      (node (ref "C13") (pin "1") (pinfunction "1_1") (pintype "passive"))
      (node (ref "C14") (pin "1") (pinfunction "1_1") (pintype "passive"))
      (node (ref "EPAPER_1") (pin "8") (pinfunction "8_8") (pintype "passive"))
      (node (ref "EPAPER_2") (pin "8") (pinfunction "8_8") (pintype "passive"))
      (node (ref "FLASH") (pin "1") (pinfunction "1_1") (pintype "passive"))
      (node (ref "FLASH") (pin "2") (pinfunction "2_2") (pintype "passive"))
      (node (ref "POWER") (pin "1") (pinfunction "1_1") (pintype "passive"))
      (node (ref "POWER") (pin "11") (pinfunction "11_11") (pintype "passive"))
      (node (ref "POWER") (pin "3") (pinfunction "3_3") (pintype "passive"))
      (node (ref "POWER_2.5V") (pin "2") (pinfunction "2_2") (pintype "passive"))
      (node (ref "USB-UART_1") (pin "3") (pinfunction "3_3") (pintype "passive"))
    )
    (net (code "164") (name "VDD_5V") (class "Default")
      (node (ref "USB-UART_2") (pin "2") (pinfunction "2_2") (pintype "passive"))
    )
    (net (code "165") (name "WAKEUP_SIGNAL") (class "Default")
      (node (ref "U2") (pin "2") (pinfunction "A_2") (pintype "input"))
      (node (ref "WAKEUP_SIGNAL") (pin "2") (pinfunction "2_2") (pintype "passive"))
    )
    (net (code "166") (name "unconnected-(FLASH-Pad5)") (class "Default")
      (node (ref "FLASH") (pin "5") (pinfunction "5_5") (pintype "passive"))
    )
    (net (code "167") (name "unconnected-(FLASH-Pad7)") (class "Default")
      (node (ref "FLASH") (pin "7") (pinfunction "7_7") (pintype "passive"))
    )
    (net (code "168") (name "unconnected-(FLASH-Pad9)") (class "Default")
      (node (ref "FLASH") (pin "9") (pinfunction "9_9") (pintype "passive"))
    )
    (net (code "169") (name "unconnected-(FLASH-Pad11)") (class "Default")
      (node (ref "FLASH") (pin "11") (pinfunction "11_11") (pintype "passive"))
    )
    (net (code "170") (name "unconnected-(IC1-NC_1-Pad1)") (class "Default")
      (node (ref "IC1") (pin "1") (pinfunction "NC_1_1") (pintype "bidirectional"))
    )
    (net (code "171") (name "unconnected-(IC1-NC_2-Pad4)") (class "Default")
      (node (ref "IC1") (pin "4") (pinfunction "NC_2_4") (pintype "bidirectional"))
    )
    (net (code "172") (name "unconnected-(IC1-NC_3-Pad5)") (class "Default")
      (node (ref "IC1") (pin "5") (pinfunction "NC_3_5") (pintype "bidirectional"))
    )
    (net (code "173") (name "unconnected-(IC2-NC_1-Pad1)") (class "Default")
      (node (ref "IC2") (pin "1") (pinfunction "NC_1_1") (pintype "bidirectional"))
    )
    (net (code "174") (name "unconnected-(IC2-NC_2-Pad4)") (class "Default")
      (node (ref "IC2") (pin "4") (pinfunction "NC_2_4") (pintype "bidirectional"))
    )
    (net (code "175") (name "unconnected-(IC2-NC_3-Pad5)") (class "Default")
      (node (ref "IC2") (pin "5") (pinfunction "NC_3_5") (pintype "bidirectional"))
    )
    (net (code "176") (name "unconnected-(IC3-NC_1-Pad1)") (class "Default")
      (node (ref "IC3") (pin "1") (pinfunction "NC_1_1") (pintype "bidirectional"))
    )
    (net (code "177") (name "unconnected-(IC3-NC_2-Pad4)") (class "Default")
      (node (ref "IC3") (pin "4") (pinfunction "NC_2_4") (pintype "bidirectional"))
    )
    (net (code "178") (name "unconnected-(IC3-NC_3-Pad5)") (class "Default")
      (node (ref "IC3") (pin "5") (pinfunction "NC_3_5") (pintype "bidirectional"))
    )
    (net (code "179") (name "unconnected-(U$1-Pad2)") (class "Default")
      (node (ref "U$1") (pin "2") (pinfunction "2_2") (pintype "bidirectional"))
    )
    (net (code "180") (name "unconnected-(U$1-Pad41)") (class "Default")
      (node (ref "U$1") (pin "41") (pinfunction "41_41") (pintype "bidirectional"))
    )
    (net (code "181") (name "unconnected-(U$2-Pad2)") (class "Default")
      (node (ref "U$2") (pin "2") (pinfunction "2_2") (pintype "bidirectional"))
    )
    (net (code "182") (name "unconnected-(U$2-Pad41)") (class "Default")
      (node (ref "U$2") (pin "41") (pinfunction "41_41") (pintype "bidirectional"))
    )
    (net (code "183") (name "unconnected-(U$3-Pad2)") (class "Default")
      (node (ref "U$3") (pin "2") (pinfunction "2_2") (pintype "bidirectional"))
    )
    (net (code "184") (name "unconnected-(U$3-Pad41)") (class "Default")
      (node (ref "U$3") (pin "41") (pinfunction "41_41") (pintype "bidirectional"))
    )
    (net (code "185") (name "unconnected-(U$4-Pad2)") (class "Default")
      (node (ref "U$4") (pin "2") (pinfunction "2_2") (pintype "bidirectional"))
    )
    (net (code "186") (name "unconnected-(U$4-Pad41)") (class "Default")
      (node (ref "U$4") (pin "41") (pinfunction "41_41") (pintype "bidirectional"))
    )
    (net (code "187") (name "unconnected-(U2-N{slash}C-Pad1)") (class "Default")
      (node (ref "U2") (pin "1") (pinfunction "N/C_1") (pintype "no_connect"))
    )
    (net (code "188") (name "unconnected-(U3-N{slash}C-Pad1)") (class "Default")
      (node (ref "U3") (pin "1") (pinfunction "N/C_1") (pintype "no_connect"))
    )
    (net (code "189") (name "unconnected-(USB-UART_2-Pad1)") (class "Default")
      (node (ref "USB-UART_2") (pin "1") (pinfunction "1_1") (pintype "passive"))
    )
    (net (code "190") (name "unconnected-(USB-UART_2-Pad3)") (class "Default")
      (node (ref "USB-UART_2") (pin "3") (pinfunction "3_3") (pintype "passive"))
    )
    (net (code "191") (name "unconnected-(USB-UART_2-Pad4)") (class "Default")
      (node (ref "USB-UART_2") (pin "4") (pinfunction "4_4") (pintype "passive"))
    )
  )
)
